# relayinput4.net
KiCad netlist of a schematic drawn in EAGLE
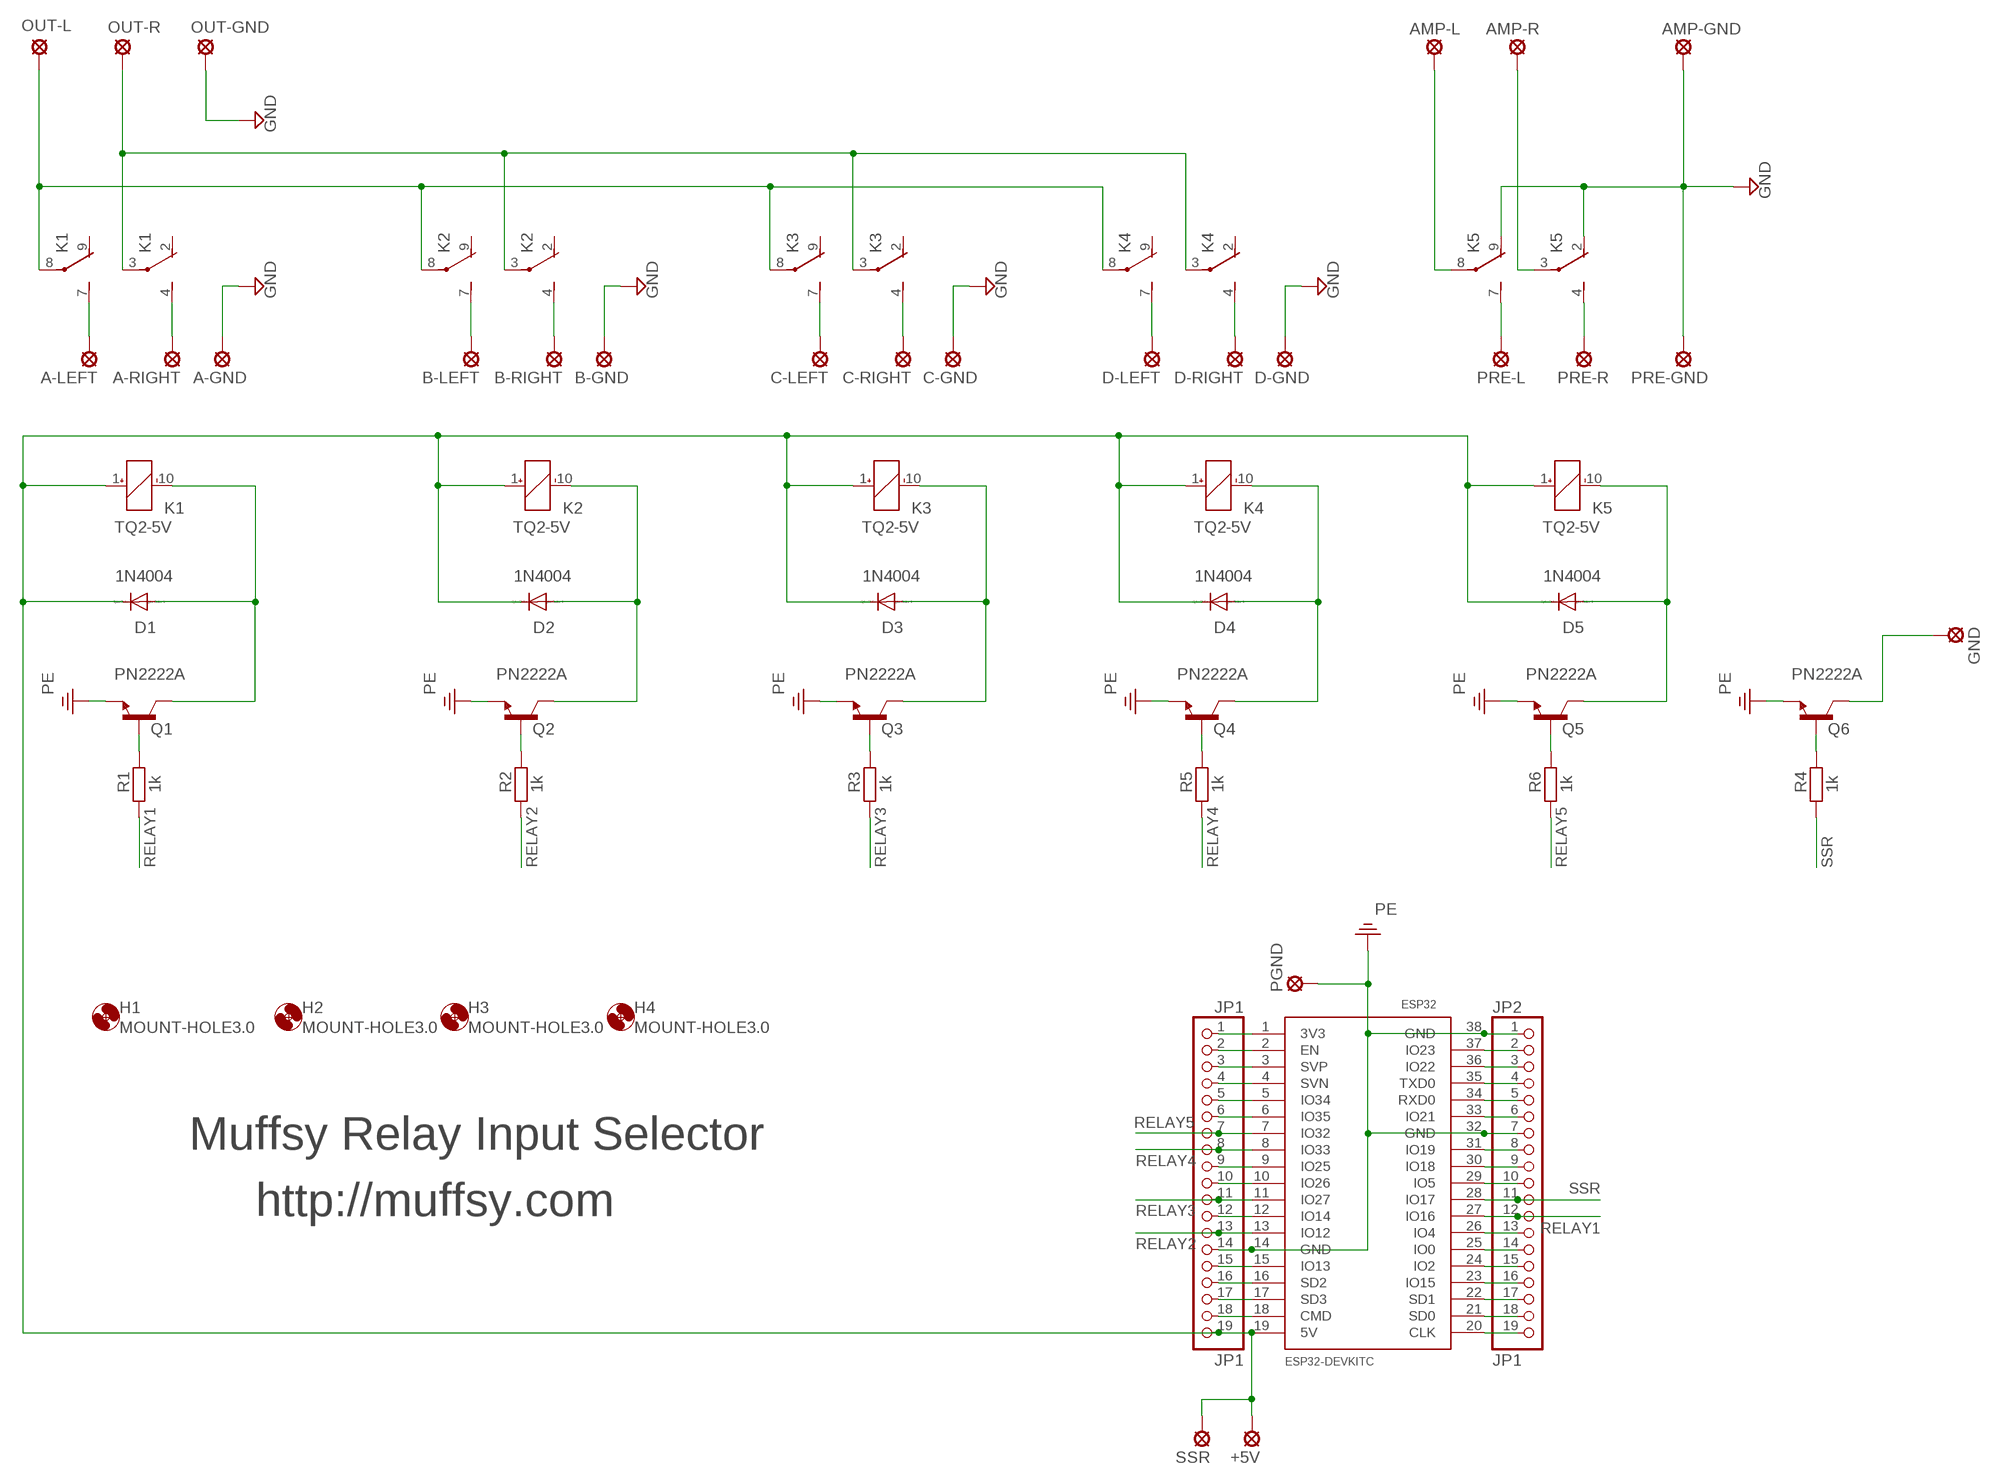
[diagram p0: schematic, sheet 1]

(export (version "E")
  (design (tool "Eeschema 10.0.6"))
  (components
    (comp (ref "+5V")
      (value "SE11")
      (footprint "eagle-import:SE11")
      (libsource (lib "eagle-import") (part "SE11"))
    )
    (comp (ref "A-GND")
      (value "SE11")
      (footprint "eagle-import:SE11")
      (libsource (lib "eagle-import") (part "SE11"))
    )
    (comp (ref "A-LEFT")
      (value "SE11")
      (footprint "eagle-import:SE11")
      (libsource (lib "eagle-import") (part "SE11"))
    )
    (comp (ref "A-RIGHT")
      (value "SE11")
      (footprint "eagle-import:SE11")
      (libsource (lib "eagle-import") (part "SE11"))
    )
    (comp (ref "AMP-GND")
      (value "SE11")
      (footprint "eagle-import:SE11")
      (libsource (lib "eagle-import") (part "SE11"))
    )
    (comp (ref "AMP-L")
      (value "SE11")
      (footprint "eagle-import:SE11")
      (libsource (lib "eagle-import") (part "SE11"))
    )
    (comp (ref "AMP-R")
      (value "SE11")
      (footprint "eagle-import:SE11")
      (libsource (lib "eagle-import") (part "SE11"))
    )
    (comp (ref "B-GND")
      (value "SE11")
      (footprint "eagle-import:SE11")
      (libsource (lib "eagle-import") (part "SE11"))
    )
    (comp (ref "B-LEFT")
      (value "SE11")
      (footprint "eagle-import:SE11")
      (libsource (lib "eagle-import") (part "SE11"))
    )
    (comp (ref "B-RIGHT")
      (value "SE11")
      (footprint "eagle-import:SE11")
      (libsource (lib "eagle-import") (part "SE11"))
    )
    (comp (ref "C-GND")
      (value "SE11")
      (footprint "eagle-import:SE11")
      (libsource (lib "eagle-import") (part "SE11"))
    )
    (comp (ref "C-LEFT")
      (value "SE11")
      (footprint "eagle-import:SE11")
      (libsource (lib "eagle-import") (part "SE11"))
    )
    (comp (ref "C-RIGHT")
      (value "SE11")
      (footprint "eagle-import:SE11")
      (libsource (lib "eagle-import") (part "SE11"))
    )
    (comp (ref "D-GND")
      (value "SE11")
      (footprint "eagle-import:SE11")
      (libsource (lib "eagle-import") (part "SE11"))
    )
    (comp (ref "D-LEFT")
      (value "SE11")
      (footprint "eagle-import:SE11")
      (libsource (lib "eagle-import") (part "SE11"))
    )
    (comp (ref "D-RIGHT")
      (value "SE11")
      (footprint "eagle-import:SE11")
      (libsource (lib "eagle-import") (part "SE11"))
    )
    (comp (ref "D1")
      (value "1N4004")
      (footprint "eagle-import:DO41-10")
      (libsource (lib "eagle-import") (part "1N4004"))
    )
    (comp (ref "D2")
      (value "1N4004")
      (footprint "eagle-import:DO41-10")
      (libsource (lib "eagle-import") (part "1N4004"))
    )
    (comp (ref "D3")
      (value "1N4004")
      (footprint "eagle-import:DO41-10")
      (libsource (lib "eagle-import") (part "1N4004"))
    )
    (comp (ref "D4")
      (value "1N4004")
      (footprint "eagle-import:DO41-10")
      (libsource (lib "eagle-import") (part "1N4004"))
    )
    (comp (ref "D5")
      (value "1N4004")
      (footprint "eagle-import:DO41-10")
      (libsource (lib "eagle-import") (part "1N4004"))
    )
    (comp (ref "ESP32")
      (value "ESP32DEVKITC")
      (footprint "eagle-import:ESP32-DEVKITC")
      (libsource (lib "eagle-import") (part "ESP32DEVKITC"))
    )
    (comp (ref "GND")
      (value "SE11")
      (footprint "eagle-import:SE11")
      (libsource (lib "eagle-import") (part "SE11"))
    )
    (comp (ref "H1")
      (value "MOUNT-HOLE3.0")
      (footprint "eagle-import:3,0")
      (libsource (lib "eagle-import") (part "MOUNT-HOLE3.0"))
    )
    (comp (ref "H2")
      (value "MOUNT-HOLE3.0")
      (footprint "eagle-import:3,0")
      (libsource (lib "eagle-import") (part "MOUNT-HOLE3.0"))
    )
    (comp (ref "H3")
      (value "MOUNT-HOLE3.0")
      (footprint "eagle-import:3,0")
      (libsource (lib "eagle-import") (part "MOUNT-HOLE3.0"))
    )
    (comp (ref "H4")
      (value "MOUNT-HOLE3.0")
      (footprint "eagle-import:3,0")
      (libsource (lib "eagle-import") (part "MOUNT-HOLE3.0"))
    )
    (comp (ref "JP1")
      (value "JP1")
      (footprint "eagle-import:1X19")
      (libsource (lib "eagle-import") (part "PINHD-1X19"))
    )
    (comp (ref "JP2")
      (value "JP1")
      (footprint "eagle-import:1X19")
      (libsource (lib "eagle-import") (part "PINHD-1X19"))
    )
    (comp (ref "K1")
      (value "TQ2-5V")
      (footprint "eagle-import:TQ2")
      (fields (field (name "MF") "AROMAT/ MATSUSHITA") (field (name "MPN") "TQ2-12V"))
      (libsource (lib "eagle-import") (part "TQ2?-12V"))
    )
    (comp (ref "K2")
      (value "TQ2-5V")
      (footprint "eagle-import:TQ2")
      (fields (field (name "MF") "AROMAT/ MATSUSHITA") (field (name "MPN") "TQ2-12V"))
      (libsource (lib "eagle-import") (part "TQ2?-12V"))
    )
    (comp (ref "K3")
      (value "TQ2-5V")
      (footprint "eagle-import:TQ2")
      (fields (field (name "MF") "AROMAT/ MATSUSHITA") (field (name "MPN") "TQ2-12V"))
      (libsource (lib "eagle-import") (part "TQ2?-12V"))
    )
    (comp (ref "K4")
      (value "TQ2-5V")
      (footprint "eagle-import:TQ2")
      (fields (field (name "MF") "AROMAT/ MATSUSHITA") (field (name "MPN") "TQ2-12V"))
      (libsource (lib "eagle-import") (part "TQ2?-12V"))
    )
    (comp (ref "K5")
      (value "TQ2-5V")
      (footprint "eagle-import:TQ2")
      (fields (field (name "MF") "AROMAT/ MATSUSHITA") (field (name "MPN") "TQ2-12V"))
      (libsource (lib "eagle-import") (part "TQ2?-12V"))
    )
    (comp (ref "OUT-GND")
      (value "SE11")
      (footprint "eagle-import:SE11")
      (libsource (lib "eagle-import") (part "SE11"))
    )
    (comp (ref "OUT-L")
      (value "SE11")
      (footprint "eagle-import:SE11")
      (libsource (lib "eagle-import") (part "SE11"))
    )
    (comp (ref "OUT-R")
      (value "SE11")
      (footprint "eagle-import:SE11")
      (libsource (lib "eagle-import") (part "SE11"))
    )
    (comp (ref "PGND")
      (value "SE11")
      (footprint "eagle-import:SE11")
      (libsource (lib "eagle-import") (part "SE11"))
    )
    (comp (ref "PRE-GND")
      (value "SE11")
      (footprint "eagle-import:SE11")
      (libsource (lib "eagle-import") (part "SE11"))
    )
    (comp (ref "PRE-L")
      (value "SE11")
      (footprint "eagle-import:SE11")
      (libsource (lib "eagle-import") (part "SE11"))
    )
    (comp (ref "PRE-R")
      (value "SE11")
      (footprint "eagle-import:SE11")
      (libsource (lib "eagle-import") (part "SE11"))
    )
    (comp (ref "Q1")
      (value "PN2222A")
      (footprint "eagle-import:TO92")
      (fields (field (name "MF") "STMicroelectronics"))
      (libsource (lib "eagle-import") (part "PN2222A"))
    )
    (comp (ref "Q2")
      (value "PN2222A")
      (footprint "eagle-import:TO92")
      (fields (field (name "MF") "STMicroelectronics"))
      (libsource (lib "eagle-import") (part "PN2222A"))
    )
    (comp (ref "Q3")
      (value "PN2222A")
      (footprint "eagle-import:TO92")
      (fields (field (name "MF") "STMicroelectronics"))
      (libsource (lib "eagle-import") (part "PN2222A"))
    )
    (comp (ref "Q4")
      (value "PN2222A")
      (footprint "eagle-import:TO92")
      (fields (field (name "MF") "STMicroelectronics"))
      (libsource (lib "eagle-import") (part "PN2222A"))
    )
    (comp (ref "Q5")
      (value "PN2222A")
      (footprint "eagle-import:TO92")
      (fields (field (name "MF") "STMicroelectronics"))
      (libsource (lib "eagle-import") (part "PN2222A"))
    )
    (comp (ref "Q6")
      (value "PN2222A")
      (footprint "eagle-import:TO92")
      (fields (field (name "MF") "STMicroelectronics"))
      (libsource (lib "eagle-import") (part "PN2222A"))
    )
    (comp (ref "R1")
      (value "1k")
      (footprint "eagle-import:0207_10")
      (libsource (lib "eagle-import") (part "R-EU_0207/10"))
    )
    (comp (ref "R2")
      (value "1k")
      (footprint "eagle-import:0207_10")
      (libsource (lib "eagle-import") (part "R-EU_0207/10"))
    )
    (comp (ref "R3")
      (value "1k")
      (footprint "eagle-import:0207_10")
      (libsource (lib "eagle-import") (part "R-EU_0207/10"))
    )
    (comp (ref "R4")
      (value "1k")
      (footprint "eagle-import:0207_10")
      (libsource (lib "eagle-import") (part "R-EU_0207/10"))
    )
    (comp (ref "R5")
      (value "1k")
      (footprint "eagle-import:0207_10")
      (libsource (lib "eagle-import") (part "R-EU_0207/10"))
    )
    (comp (ref "R6")
      (value "1k")
      (footprint "eagle-import:0207_10")
      (libsource (lib "eagle-import") (part "R-EU_0207/10"))
    )
    (comp (ref "SSR")
      (value "SE11")
      (footprint "eagle-import:SE11")
      (libsource (lib "eagle-import") (part "SE11"))
    )
  )
  (nets
    (net (code "1") (name "GND") (class "Default")
      (node (ref "A-GND") (pin "MP") (pinfunction "MP_MP") (pintype "passive"))
      (node (ref "AMP-GND") (pin "MP") (pinfunction "MP_MP") (pintype "passive"))
      (node (ref "B-GND") (pin "MP") (pinfunction "MP_MP") (pintype "passive"))
      (node (ref "C-GND") (pin "MP") (pinfunction "MP_MP") (pintype "passive"))
      (node (ref "D-GND") (pin "MP") (pinfunction "MP_MP") (pintype "passive"))
      (node (ref "K5") (pin "2") (pinfunction "O_2") (pintype "passive"))
      (node (ref "K5") (pin "9") (pinfunction "O_9") (pintype "passive"))
      (node (ref "OUT-GND") (pin "MP") (pinfunction "MP_MP") (pintype "passive"))
      (node (ref "PRE-GND") (pin "MP") (pinfunction "MP_MP") (pintype "passive"))
    )
    (net (code "2") (name "Net-(ESP32-3V3)") (class "Default")
      (node (ref "ESP32") (pin "1") (pinfunction "3V3_1") (pintype "bidirectional"))
      (node (ref "JP1") (pin "1") (pinfunction "1_1") (pintype "passive"))
    )
    (net (code "3") (name "Net-(ESP32-5V)") (class "Default")
      (node (ref "+5V") (pin "MP") (pinfunction "MP_MP") (pintype "passive"))
      (node (ref "D1") (pin "C") (pinfunction "C_C") (pintype "passive"))
      (node (ref "D2") (pin "C") (pinfunction "C_C") (pintype "passive"))
      (node (ref "D3") (pin "C") (pinfunction "C_C") (pintype "passive"))
      (node (ref "D4") (pin "C") (pinfunction "C_C") (pintype "passive"))
      (node (ref "D5") (pin "C") (pinfunction "C_C") (pintype "passive"))
      (node (ref "ESP32") (pin "19") (pinfunction "5V_19") (pintype "bidirectional"))
      (node (ref "JP1") (pin "19") (pinfunction "19_19") (pintype "passive"))
      (node (ref "K1") (pin "1") (pinfunction "+_1") (pintype "passive"))
      (node (ref "K2") (pin "1") (pinfunction "+_1") (pintype "passive"))
      (node (ref "K3") (pin "1") (pinfunction "+_1") (pintype "passive"))
      (node (ref "K4") (pin "1") (pinfunction "+_1") (pintype "passive"))
      (node (ref "K5") (pin "1") (pinfunction "+_1") (pintype "passive"))
      (node (ref "SSR") (pin "MP") (pinfunction "MP_MP") (pintype "passive"))
    )
    (net (code "4") (name "Net-(ESP32-CLK)") (class "Default")
      (node (ref "ESP32") (pin "20") (pinfunction "CLK_20") (pintype "bidirectional"))
      (node (ref "JP2") (pin "19") (pinfunction "19_19") (pintype "passive"))
    )
    (net (code "5") (name "Net-(ESP32-CMD)") (class "Default")
      (node (ref "ESP32") (pin "18") (pinfunction "CMD_18") (pintype "bidirectional"))
      (node (ref "JP1") (pin "18") (pinfunction "18_18") (pintype "passive"))
    )
    (net (code "6") (name "Net-(ESP32-EN)") (class "Default")
      (node (ref "ESP32") (pin "2") (pinfunction "EN_2") (pintype "bidirectional"))
      (node (ref "JP1") (pin "2") (pinfunction "2_2") (pintype "passive"))
    )
    (net (code "7") (name "Net-(ESP32-IO0)") (class "Default")
      (node (ref "ESP32") (pin "25") (pinfunction "IO0_25") (pintype "bidirectional"))
      (node (ref "JP2") (pin "14") (pinfunction "14_14") (pintype "passive"))
    )
    (net (code "8") (name "Net-(ESP32-IO2)") (class "Default")
      (node (ref "ESP32") (pin "24") (pinfunction "IO2_24") (pintype "bidirectional"))
      (node (ref "JP2") (pin "15") (pinfunction "15_15") (pintype "passive"))
    )
    (net (code "9") (name "Net-(ESP32-IO4)") (class "Default")
      (node (ref "ESP32") (pin "26") (pinfunction "IO4_26") (pintype "bidirectional"))
      (node (ref "JP2") (pin "13") (pinfunction "13_13") (pintype "passive"))
    )
    (net (code "10") (name "Net-(ESP32-IO5)") (class "Default")
      (node (ref "ESP32") (pin "29") (pinfunction "IO5_29") (pintype "bidirectional"))
      (node (ref "JP2") (pin "10") (pinfunction "10_10") (pintype "passive"))
    )
    (net (code "11") (name "Net-(ESP32-IO13)") (class "Default")
      (node (ref "ESP32") (pin "15") (pinfunction "IO13_15") (pintype "bidirectional"))
      (node (ref "JP1") (pin "15") (pinfunction "15_15") (pintype "passive"))
    )
    (net (code "12") (name "Net-(ESP32-IO14)") (class "Default")
      (node (ref "ESP32") (pin "12") (pinfunction "IO14_12") (pintype "bidirectional"))
      (node (ref "JP1") (pin "12") (pinfunction "12_12") (pintype "passive"))
    )
    (net (code "13") (name "Net-(ESP32-IO15)") (class "Default")
      (node (ref "ESP32") (pin "23") (pinfunction "IO15_23") (pintype "bidirectional"))
      (node (ref "JP2") (pin "16") (pinfunction "16_16") (pintype "passive"))
    )
    (net (code "14") (name "Net-(ESP32-IO18)") (class "Default")
      (node (ref "ESP32") (pin "30") (pinfunction "IO18_30") (pintype "bidirectional"))
      (node (ref "JP2") (pin "9") (pinfunction "9_9") (pintype "passive"))
    )
    (net (code "15") (name "Net-(ESP32-IO19)") (class "Default")
      (node (ref "ESP32") (pin "31") (pinfunction "IO19_31") (pintype "bidirectional"))
      (node (ref "JP2") (pin "8") (pinfunction "8_8") (pintype "passive"))
    )
    (net (code "16") (name "Net-(ESP32-IO21)") (class "Default")
      (node (ref "ESP32") (pin "33") (pinfunction "IO21_33") (pintype "bidirectional"))
      (node (ref "JP2") (pin "6") (pinfunction "6_6") (pintype "passive"))
    )
    (net (code "17") (name "Net-(ESP32-IO22)") (class "Default")
      (node (ref "ESP32") (pin "36") (pinfunction "IO22_36") (pintype "bidirectional"))
      (node (ref "JP2") (pin "3") (pinfunction "3_3") (pintype "passive"))
    )
    (net (code "18") (name "Net-(ESP32-IO23)") (class "Default")
      (node (ref "ESP32") (pin "37") (pinfunction "IO23_37") (pintype "bidirectional"))
      (node (ref "JP2") (pin "2") (pinfunction "2_2") (pintype "passive"))
    )
    (net (code "19") (name "Net-(ESP32-IO25)") (class "Default")
      (node (ref "ESP32") (pin "9") (pinfunction "IO25_9") (pintype "bidirectional"))
      (node (ref "JP1") (pin "9") (pinfunction "9_9") (pintype "passive"))
    )
    (net (code "20") (name "Net-(ESP32-IO26)") (class "Default")
      (node (ref "ESP32") (pin "10") (pinfunction "IO26_10") (pintype "bidirectional"))
      (node (ref "JP1") (pin "10") (pinfunction "10_10") (pintype "passive"))
    )
    (net (code "21") (name "Net-(ESP32-IO34)") (class "Default")
      (node (ref "ESP32") (pin "5") (pinfunction "IO34_5") (pintype "bidirectional"))
      (node (ref "JP1") (pin "5") (pinfunction "5_5") (pintype "passive"))
    )
    (net (code "22") (name "Net-(ESP32-IO35)") (class "Default")
      (node (ref "ESP32") (pin "6") (pinfunction "IO35_6") (pintype "bidirectional"))
      (node (ref "JP1") (pin "6") (pinfunction "6_6") (pintype "passive"))
    )
    (net (code "23") (name "Net-(ESP32-RXD0)") (class "Default")
      (node (ref "ESP32") (pin "34") (pinfunction "RXD0_34") (pintype "bidirectional"))
      (node (ref "JP2") (pin "5") (pinfunction "5_5") (pintype "passive"))
    )
    (net (code "24") (name "Net-(ESP32-SD0)") (class "Default")
      (node (ref "ESP32") (pin "21") (pinfunction "SD0_21") (pintype "bidirectional"))
      (node (ref "JP2") (pin "18") (pinfunction "18_18") (pintype "passive"))
    )
    (net (code "25") (name "Net-(ESP32-SD1)") (class "Default")
      (node (ref "ESP32") (pin "22") (pinfunction "SD1_22") (pintype "bidirectional"))
      (node (ref "JP2") (pin "17") (pinfunction "17_17") (pintype "passive"))
    )
    (net (code "26") (name "Net-(ESP32-SD2)") (class "Default")
      (node (ref "ESP32") (pin "16") (pinfunction "SD2_16") (pintype "bidirectional"))
      (node (ref "JP1") (pin "16") (pinfunction "16_16") (pintype "passive"))
    )
    (net (code "27") (name "Net-(ESP32-SD3)") (class "Default")
      (node (ref "ESP32") (pin "17") (pinfunction "SD3_17") (pintype "bidirectional"))
      (node (ref "JP1") (pin "17") (pinfunction "17_17") (pintype "passive"))
    )
    (net (code "28") (name "Net-(ESP32-SVN)") (class "Default")
      (node (ref "ESP32") (pin "4") (pinfunction "SVN_4") (pintype "bidirectional"))
      (node (ref "JP1") (pin "4") (pinfunction "4_4") (pintype "passive"))
    )
    (net (code "29") (name "Net-(ESP32-SVP)") (class "Default")
      (node (ref "ESP32") (pin "3") (pinfunction "SVP_3") (pintype "bidirectional"))
      (node (ref "JP1") (pin "3") (pinfunction "3_3") (pintype "passive"))
    )
    (net (code "30") (name "Net-(ESP32-TXD0)") (class "Default")
      (node (ref "ESP32") (pin "35") (pinfunction "TXD0_35") (pintype "bidirectional"))
      (node (ref "JP2") (pin "4") (pinfunction "4_4") (pintype "passive"))
    )
    (net (code "31") (name "Net-(GND-PadMP)") (class "Default")
      (node (ref "GND") (pin "MP") (pinfunction "MP_MP") (pintype "passive"))
      (node (ref "Q6") (pin "C") (pinfunction "C_C") (pintype "passive"))
    )
    (net (code "32") (name "Net-(K1A-P)") (class "Default")
      (node (ref "K1") (pin "3") (pinfunction "P_3") (pintype "passive"))
      (node (ref "K2") (pin "3") (pinfunction "P_3") (pintype "passive"))
      (node (ref "K3") (pin "3") (pinfunction "P_3") (pintype "passive"))
      (node (ref "K4") (pin "3") (pinfunction "P_3") (pintype "passive"))
      (node (ref "OUT-R") (pin "MP") (pinfunction "MP_MP") (pintype "passive"))
    )
    (net (code "33") (name "Net-(K1A-S)") (class "Default")
      (node (ref "A-RIGHT") (pin "MP") (pinfunction "MP_MP") (pintype "passive"))
      (node (ref "K1") (pin "4") (pinfunction "S_4") (pintype "passive"))
    )
    (net (code "34") (name "Net-(K1B-P)") (class "Default")
      (node (ref "K1") (pin "8") (pinfunction "P_8") (pintype "passive"))
      (node (ref "K2") (pin "8") (pinfunction "P_8") (pintype "passive"))
      (node (ref "K3") (pin "8") (pinfunction "P_8") (pintype "passive"))
      (node (ref "K4") (pin "8") (pinfunction "P_8") (pintype "passive"))
      (node (ref "OUT-L") (pin "MP") (pinfunction "MP_MP") (pintype "passive"))
    )
    (net (code "35") (name "Net-(K1B-S)") (class "Default")
      (node (ref "A-LEFT") (pin "MP") (pinfunction "MP_MP") (pintype "passive"))
      (node (ref "K1") (pin "7") (pinfunction "S_7") (pintype "passive"))
    )
    (net (code "36") (name "Net-(K1C--)") (class "Default")
      (node (ref "D1") (pin "A") (pinfunction "A_A") (pintype "passive"))
      (node (ref "K1") (pin "10") (pinfunction "-_10") (pintype "passive"))
      (node (ref "Q1") (pin "C") (pinfunction "C_C") (pintype "passive"))
    )
    (net (code "37") (name "Net-(K2A-S)") (class "Default")
      (node (ref "B-RIGHT") (pin "MP") (pinfunction "MP_MP") (pintype "passive"))
      (node (ref "K2") (pin "4") (pinfunction "S_4") (pintype "passive"))
    )
    (net (code "38") (name "Net-(K2B-S)") (class "Default")
      (node (ref "B-LEFT") (pin "MP") (pinfunction "MP_MP") (pintype "passive"))
      (node (ref "K2") (pin "7") (pinfunction "S_7") (pintype "passive"))
    )
    (net (code "39") (name "Net-(K2C--)") (class "Default")
      (node (ref "D2") (pin "A") (pinfunction "A_A") (pintype "passive"))
      (node (ref "K2") (pin "10") (pinfunction "-_10") (pintype "passive"))
      (node (ref "Q2") (pin "C") (pinfunction "C_C") (pintype "passive"))
    )
    (net (code "40") (name "Net-(K3A-S)") (class "Default")
      (node (ref "C-RIGHT") (pin "MP") (pinfunction "MP_MP") (pintype "passive"))
      (node (ref "K3") (pin "4") (pinfunction "S_4") (pintype "passive"))
    )
    (net (code "41") (name "Net-(K3B-S)") (class "Default")
      (node (ref "C-LEFT") (pin "MP") (pinfunction "MP_MP") (pintype "passive"))
      (node (ref "K3") (pin "7") (pinfunction "S_7") (pintype "passive"))
    )
    (net (code "42") (name "Net-(K3C--)") (class "Default")
      (node (ref "D3") (pin "A") (pinfunction "A_A") (pintype "passive"))
      (node (ref "K3") (pin "10") (pinfunction "-_10") (pintype "passive"))
      (node (ref "Q3") (pin "C") (pinfunction "C_C") (pintype "passive"))
    )
    (net (code "43") (name "Net-(K4A-S)") (class "Default")
      (node (ref "D-RIGHT") (pin "MP") (pinfunction "MP_MP") (pintype "passive"))
      (node (ref "K4") (pin "4") (pinfunction "S_4") (pintype "passive"))
    )
    (net (code "44") (name "Net-(K4B-S)") (class "Default")
      (node (ref "D-LEFT") (pin "MP") (pinfunction "MP_MP") (pintype "passive"))
      (node (ref "K4") (pin "7") (pinfunction "S_7") (pintype "passive"))
    )
    (net (code "45") (name "Net-(K4C--)") (class "Default")
      (node (ref "D4") (pin "A") (pinfunction "A_A") (pintype "passive"))
      (node (ref "K4") (pin "10") (pinfunction "-_10") (pintype "passive"))
      (node (ref "Q4") (pin "C") (pinfunction "C_C") (pintype "passive"))
    )
    (net (code "46") (name "Net-(K5A-P)") (class "Default")
      (node (ref "AMP-R") (pin "MP") (pinfunction "MP_MP") (pintype "passive"))
      (node (ref "K5") (pin "3") (pinfunction "P_3") (pintype "passive"))
    )
    (net (code "47") (name "Net-(K5A-S)") (class "Default")
      (node (ref "K5") (pin "4") (pinfunction "S_4") (pintype "passive"))
      (node (ref "PRE-R") (pin "MP") (pinfunction "MP_MP") (pintype "passive"))
    )
    (net (code "48") (name "Net-(K5B-P)") (class "Default")
      (node (ref "AMP-L") (pin "MP") (pinfunction "MP_MP") (pintype "passive"))
      (node (ref "K5") (pin "8") (pinfunction "P_8") (pintype "passive"))
    )
    (net (code "49") (name "Net-(K5B-S)") (class "Default")
      (node (ref "K5") (pin "7") (pinfunction "S_7") (pintype "passive"))
      (node (ref "PRE-L") (pin "MP") (pinfunction "MP_MP") (pintype "passive"))
    )
    (net (code "50") (name "Net-(K5C--)") (class "Default")
      (node (ref "D5") (pin "A") (pinfunction "A_A") (pintype "passive"))
      (node (ref "K5") (pin "10") (pinfunction "-_10") (pintype "passive"))
      (node (ref "Q5") (pin "C") (pinfunction "C_C") (pintype "passive"))
    )
    (net (code "51") (name "Net-(Q1-PadB)") (class "Default")
      (node (ref "Q1") (pin "B") (pinfunction "B_B") (pintype "passive"))
      (node (ref "R1") (pin "2") (pinfunction "2_2") (pintype "passive"))
    )
    (net (code "52") (name "Net-(Q2-PadB)") (class "Default")
      (node (ref "Q2") (pin "B") (pinfunction "B_B") (pintype "passive"))
      (node (ref "R2") (pin "2") (pinfunction "2_2") (pintype "passive"))
    )
    (net (code "53") (name "Net-(Q3-PadB)") (class "Default")
      (node (ref "Q3") (pin "B") (pinfunction "B_B") (pintype "passive"))
      (node (ref "R3") (pin "2") (pinfunction "2_2") (pintype "passive"))
    )
    (net (code "54") (name "Net-(Q4-PadB)") (class "Default")
      (node (ref "Q4") (pin "B") (pinfunction "B_B") (pintype "passive"))
      (node (ref "R5") (pin "2") (pinfunction "2_2") (pintype "passive"))
    )
    (net (code "55") (name "Net-(Q5-PadB)") (class "Default")
      (node (ref "Q5") (pin "B") (pinfunction "B_B") (pintype "passive"))
      (node (ref "R6") (pin "2") (pinfunction "2_2") (pintype "passive"))
    )
    (net (code "56") (name "Net-(Q6-PadB)") (class "Default")
      (node (ref "Q6") (pin "B") (pinfunction "B_B") (pintype "passive"))
      (node (ref "R4") (pin "2") (pinfunction "2_2") (pintype "passive"))
    )
    (net (code "57") (name "PE") (class "Default")
      (node (ref "ESP32") (pin "14") (pinfunction "GND_14") (pintype "bidirectional"))
      (node (ref "ESP32") (pin "32") (pinfunction "GND_32") (pintype "bidirectional"))
      (node (ref "ESP32") (pin "38") (pinfunction "GND_38") (pintype "bidirectional"))
      (node (ref "JP1") (pin "14") (pinfunction "14_14") (pintype "passive"))
      (node (ref "JP2") (pin "1") (pinfunction "1_1") (pintype "passive"))
      (node (ref "JP2") (pin "7") (pinfunction "7_7") (pintype "passive"))
      (node (ref "PGND") (pin "MP") (pinfunction "MP_MP") (pintype "passive"))
      (node (ref "Q1") (pin "E") (pinfunction "E_E") (pintype "passive"))
      (node (ref "Q2") (pin "E") (pinfunction "E_E") (pintype "passive"))
      (node (ref "Q3") (pin "E") (pinfunction "E_E") (pintype "passive"))
      (node (ref "Q4") (pin "E") (pinfunction "E_E") (pintype "passive"))
      (node (ref "Q5") (pin "E") (pinfunction "E_E") (pintype "passive"))
      (node (ref "Q6") (pin "E") (pinfunction "E_E") (pintype "passive"))
    )
    (net (code "58") (name "RELAY1") (class "Default")
      (node (ref "ESP32") (pin "27") (pinfunction "IO16_27") (pintype "bidirectional"))
      (node (ref "JP2") (pin "12") (pinfunction "12_12") (pintype "passive"))
      (node (ref "R1") (pin "1") (pinfunction "1_1") (pintype "passive"))
    )
    (net (code "59") (name "RELAY2") (class "Default")
      (node (ref "ESP32") (pin "13") (pinfunction "IO12_13") (pintype "bidirectional"))
      (node (ref "JP1") (pin "13") (pinfunction "13_13") (pintype "passive"))
      (node (ref "R2") (pin "1") (pinfunction "1_1") (pintype "passive"))
    )
    (net (code "60") (name "RELAY3") (class "Default")
      (node (ref "ESP32") (pin "11") (pinfunction "IO27_11") (pintype "bidirectional"))
      (node (ref "JP1") (pin "11") (pinfunction "11_11") (pintype "passive"))
      (node (ref "R3") (pin "1") (pinfunction "1_1") (pintype "passive"))
    )
    (net (code "61") (name "RELAY4") (class "Default")
      (node (ref "ESP32") (pin "8") (pinfunction "IO33_8") (pintype "bidirectional"))
      (node (ref "JP1") (pin "8") (pinfunction "8_8") (pintype "passive"))
      (node (ref "R5") (pin "1") (pinfunction "1_1") (pintype "passive"))
    )
    (net (code "62") (name "RELAY5") (class "Default")
      (node (ref "ESP32") (pin "7") (pinfunction "IO32_7") (pintype "bidirectional"))
      (node (ref "JP1") (pin "7") (pinfunction "7_7") (pintype "passive"))
      (node (ref "R6") (pin "1") (pinfunction "1_1") (pintype "passive"))
    )
    (net (code "63") (name "SSR") (class "Default")
      (node (ref "ESP32") (pin "28") (pinfunction "IO17_28") (pintype "bidirectional"))
      (node (ref "JP2") (pin "11") (pinfunction "11_11") (pintype "passive"))
      (node (ref "R4") (pin "1") (pinfunction "1_1") (pintype "passive"))
    )
    (net (code "64") (name "unconnected-(K1A-O-Pad2)") (class "Default")
      (node (ref "K1") (pin "2") (pinfunction "O_2") (pintype "passive"))
    )
    (net (code "65") (name "unconnected-(K1B-O-Pad9)") (class "Default")
      (node (ref "K1") (pin "9") (pinfunction "O_9") (pintype "passive"))
    )
    (net (code "66") (name "unconnected-(K2A-O-Pad2)") (class "Default")
      (node (ref "K2") (pin "2") (pinfunction "O_2") (pintype "passive"))
    )
    (net (code "67") (name "unconnected-(K2B-O-Pad9)") (class "Default")
      (node (ref "K2") (pin "9") (pinfunction "O_9") (pintype "passive"))
    )
    (net (code "68") (name "unconnected-(K3A-O-Pad2)") (class "Default")
      (node (ref "K3") (pin "2") (pinfunction "O_2") (pintype "passive"))
    )
    (net (code "69") (name "unconnected-(K3B-O-Pad9)") (class "Default")
      (node (ref "K3") (pin "9") (pinfunction "O_9") (pintype "passive"))
    )
    (net (code "70") (name "unconnected-(K4A-O-Pad2)") (class "Default")
      (node (ref "K4") (pin "2") (pinfunction "O_2") (pintype "passive"))
    )
    (net (code "71") (name "unconnected-(K4B-O-Pad9)") (class "Default")
      (node (ref "K4") (pin "9") (pinfunction "O_9") (pintype "passive"))
    )
  )
)
